# LED.net
KiCad netlist of a schematic drawn in EasyEDA Pro
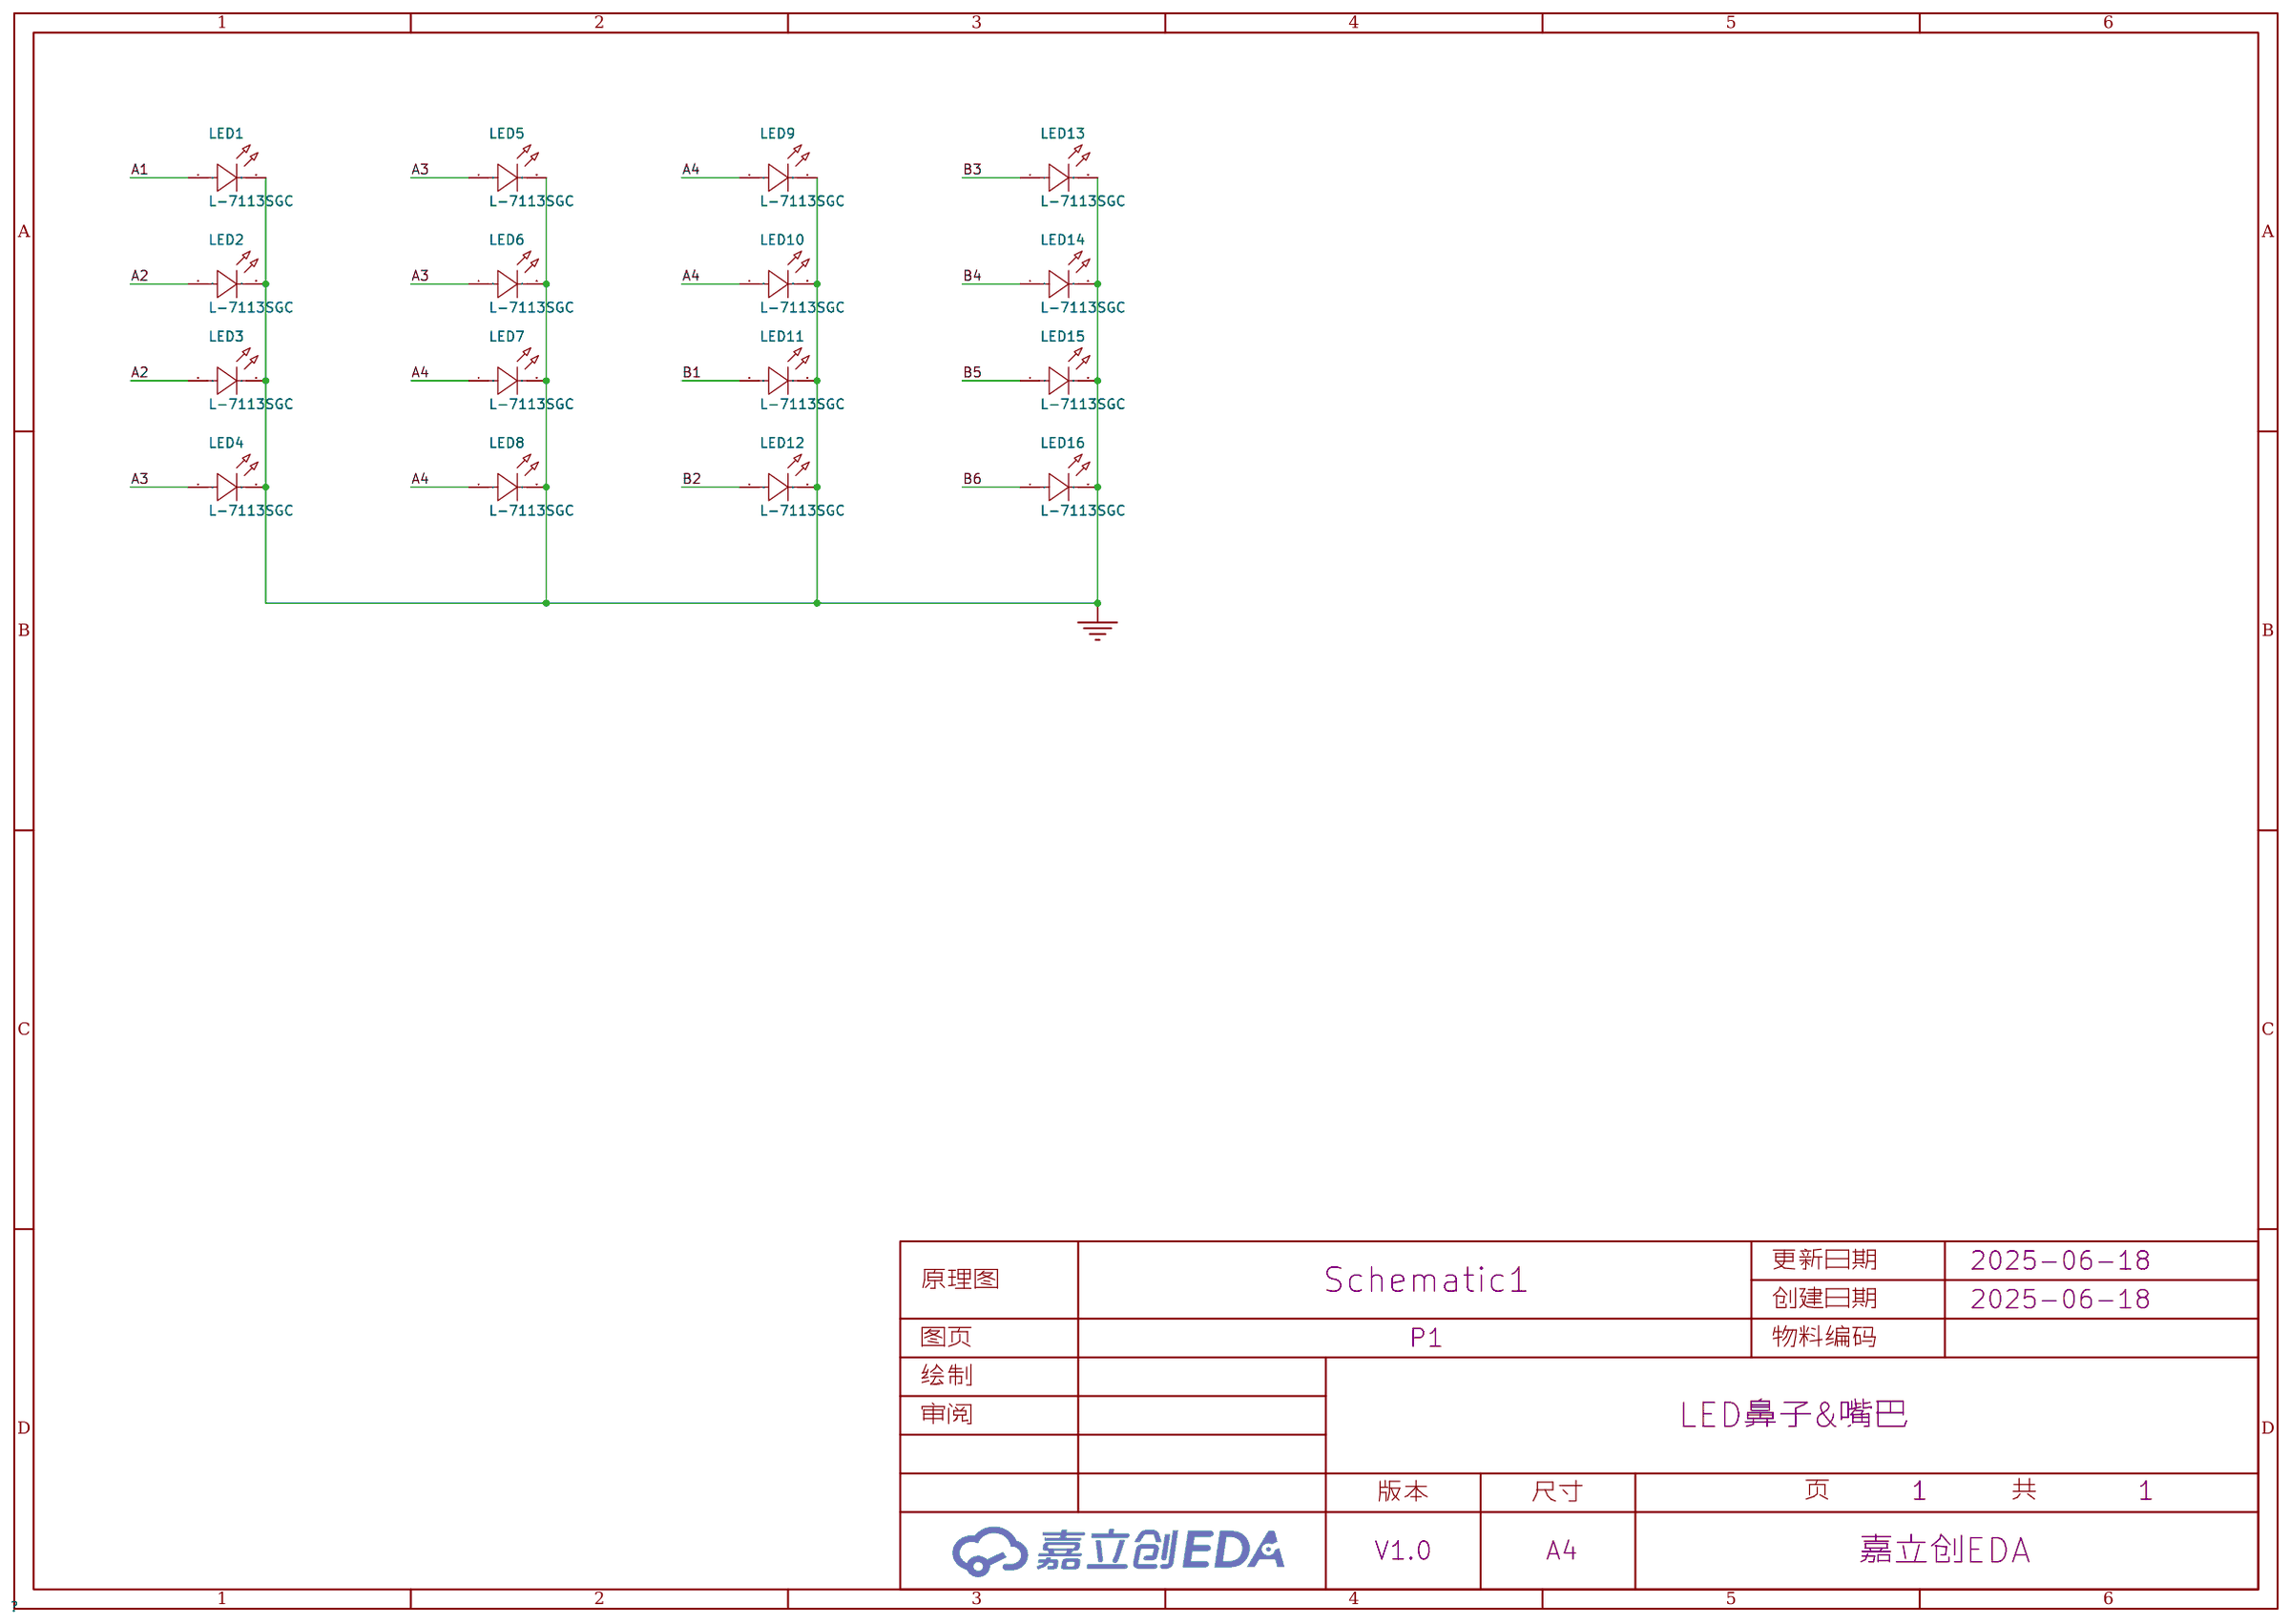
[diagram p0: schematic sheet]

(export (version "E")
  (design (tool "Eeschema 10.0.6"))
  (components
    (comp (ref "LED1")
      (value "L-7113SGC")
      (footprint "easyedapro:LED-TH_BD5.9-P2.54-FD")
      (fields (field (name "Manufacturer") "Kingbright"))
      (libsource (lib "easyedapro") (part "L-7113SGC"))
    )
    (comp (ref "LED2")
      (value "L-7113SGC")
      (footprint "easyedapro:LED-TH_BD5.9-P2.54-FD")
      (fields (field (name "Manufacturer") "Kingbright"))
      (libsource (lib "easyedapro") (part "L-7113SGC"))
    )
    (comp (ref "LED3")
      (value "L-7113SGC")
      (footprint "easyedapro:LED-TH_BD5.9-P2.54-FD")
      (fields (field (name "Manufacturer") "Kingbright"))
      (libsource (lib "easyedapro") (part "L-7113SGC"))
    )
    (comp (ref "LED4")
      (value "L-7113SGC")
      (footprint "easyedapro:LED-TH_BD5.9-P2.54-FD")
      (fields (field (name "Manufacturer") "Kingbright"))
      (libsource (lib "easyedapro") (part "L-7113SGC"))
    )
    (comp (ref "LED5")
      (value "L-7113SGC")
      (footprint "easyedapro:LED-TH_BD5.9-P2.54-FD")
      (fields (field (name "Manufacturer") "Kingbright"))
      (libsource (lib "easyedapro") (part "L-7113SGC"))
    )
    (comp (ref "LED6")
      (value "L-7113SGC")
      (footprint "easyedapro:LED-TH_BD5.9-P2.54-FD")
      (fields (field (name "Manufacturer") "Kingbright"))
      (libsource (lib "easyedapro") (part "L-7113SGC"))
    )
    (comp (ref "LED7")
      (value "L-7113SGC")
      (footprint "easyedapro:LED-TH_BD5.9-P2.54-FD")
      (fields (field (name "Manufacturer") "Kingbright"))
      (libsource (lib "easyedapro") (part "L-7113SGC"))
    )
    (comp (ref "LED8")
      (value "L-7113SGC")
      (footprint "easyedapro:LED-TH_BD5.9-P2.54-FD")
      (fields (field (name "Manufacturer") "Kingbright"))
      (libsource (lib "easyedapro") (part "L-7113SGC"))
    )
    (comp (ref "LED9")
      (value "L-7113SGC")
      (footprint "easyedapro:LED-TH_BD5.9-P2.54-FD")
      (fields (field (name "Manufacturer") "Kingbright"))
      (libsource (lib "easyedapro") (part "L-7113SGC"))
    )
    (comp (ref "LED10")
      (value "L-7113SGC")
      (footprint "easyedapro:LED-TH_BD5.9-P2.54-FD")
      (fields (field (name "Manufacturer") "Kingbright"))
      (libsource (lib "easyedapro") (part "L-7113SGC"))
    )
    (comp (ref "LED11")
      (value "L-7113SGC")
      (footprint "easyedapro:LED-TH_BD5.9-P2.54-FD")
      (fields (field (name "Manufacturer") "Kingbright"))
      (libsource (lib "easyedapro") (part "L-7113SGC"))
    )
    (comp (ref "LED12")
      (value "L-7113SGC")
      (footprint "easyedapro:LED-TH_BD5.9-P2.54-FD")
      (fields (field (name "Manufacturer") "Kingbright"))
      (libsource (lib "easyedapro") (part "L-7113SGC"))
    )
    (comp (ref "LED13")
      (value "L-7113SGC")
      (footprint "easyedapro:LED-TH_BD5.9-P2.54-FD")
      (fields (field (name "Manufacturer") "Kingbright"))
      (libsource (lib "easyedapro") (part "L-7113SGC"))
    )
    (comp (ref "LED14")
      (value "L-7113SGC")
      (footprint "easyedapro:LED-TH_BD5.9-P2.54-FD")
      (fields (field (name "Manufacturer") "Kingbright"))
      (libsource (lib "easyedapro") (part "L-7113SGC"))
    )
    (comp (ref "LED15")
      (value "L-7113SGC")
      (footprint "easyedapro:LED-TH_BD5.9-P2.54-FD")
      (fields (field (name "Manufacturer") "Kingbright"))
      (libsource (lib "easyedapro") (part "L-7113SGC"))
    )
    (comp (ref "LED16")
      (value "L-7113SGC")
      (footprint "easyedapro:LED-TH_BD5.9-P2.54-FD")
      (fields (field (name "Manufacturer") "Kingbright"))
      (libsource (lib "easyedapro") (part "L-7113SGC"))
    )
  )
  (nets
    (net (code "1") (name "/A1") (class "Default")
      (node (ref "LED1") (pin "1") (pinfunction "1_1") (pintype "unspecified"))
    )
    (net (code "2") (name "/A2") (class "Default")
      (node (ref "LED2") (pin "1") (pinfunction "1_1") (pintype "unspecified"))
      (node (ref "LED3") (pin "1") (pinfunction "1_1") (pintype "unspecified"))
    )
    (net (code "3") (name "/A3") (class "Default")
      (node (ref "LED4") (pin "1") (pinfunction "1_1") (pintype "unspecified"))
      (node (ref "LED5") (pin "1") (pinfunction "1_1") (pintype "unspecified"))
      (node (ref "LED6") (pin "1") (pinfunction "1_1") (pintype "unspecified"))
    )
    (net (code "4") (name "/A4") (class "Default")
      (node (ref "LED10") (pin "1") (pinfunction "1_1") (pintype "unspecified"))
      (node (ref "LED7") (pin "1") (pinfunction "1_1") (pintype "unspecified"))
      (node (ref "LED8") (pin "1") (pinfunction "1_1") (pintype "unspecified"))
      (node (ref "LED9") (pin "1") (pinfunction "1_1") (pintype "unspecified"))
    )
    (net (code "5") (name "/B1") (class "Default")
      (node (ref "LED11") (pin "1") (pinfunction "1_1") (pintype "unspecified"))
    )
    (net (code "6") (name "/B2") (class "Default")
      (node (ref "LED12") (pin "1") (pinfunction "1_1") (pintype "unspecified"))
    )
    (net (code "7") (name "/B3") (class "Default")
      (node (ref "LED13") (pin "1") (pinfunction "1_1") (pintype "unspecified"))
    )
    (net (code "8") (name "/B4") (class "Default")
      (node (ref "LED14") (pin "1") (pinfunction "1_1") (pintype "unspecified"))
    )
    (net (code "9") (name "/B5") (class "Default")
      (node (ref "LED15") (pin "1") (pinfunction "1_1") (pintype "unspecified"))
    )
    (net (code "10") (name "/B6") (class "Default")
      (node (ref "LED16") (pin "1") (pinfunction "1_1") (pintype "unspecified"))
    )
    (net (code "11") (name "GND") (class "Default")
      (node (ref "LED1") (pin "2") (pinfunction "2_2") (pintype "unspecified"))
      (node (ref "LED10") (pin "2") (pinfunction "2_2") (pintype "unspecified"))
      (node (ref "LED11") (pin "2") (pinfunction "2_2") (pintype "unspecified"))
      (node (ref "LED12") (pin "2") (pinfunction "2_2") (pintype "unspecified"))
      (node (ref "LED13") (pin "2") (pinfunction "2_2") (pintype "unspecified"))
      (node (ref "LED14") (pin "2") (pinfunction "2_2") (pintype "unspecified"))
      (node (ref "LED15") (pin "2") (pinfunction "2_2") (pintype "unspecified"))
      (node (ref "LED16") (pin "2") (pinfunction "2_2") (pintype "unspecified"))
      (node (ref "LED2") (pin "2") (pinfunction "2_2") (pintype "unspecified"))
      (node (ref "LED3") (pin "2") (pinfunction "2_2") (pintype "unspecified"))
      (node (ref "LED4") (pin "2") (pinfunction "2_2") (pintype "unspecified"))
      (node (ref "LED5") (pin "2") (pinfunction "2_2") (pintype "unspecified"))
      (node (ref "LED6") (pin "2") (pinfunction "2_2") (pintype "unspecified"))
      (node (ref "LED7") (pin "2") (pinfunction "2_2") (pintype "unspecified"))
      (node (ref "LED8") (pin "2") (pinfunction "2_2") (pintype "unspecified"))
      (node (ref "LED9") (pin "2") (pinfunction "2_2") (pintype "unspecified"))
    )
  )
)
